# TDA7000_SCH.net
KiCad netlist of a schematic drawn in Altium Designer
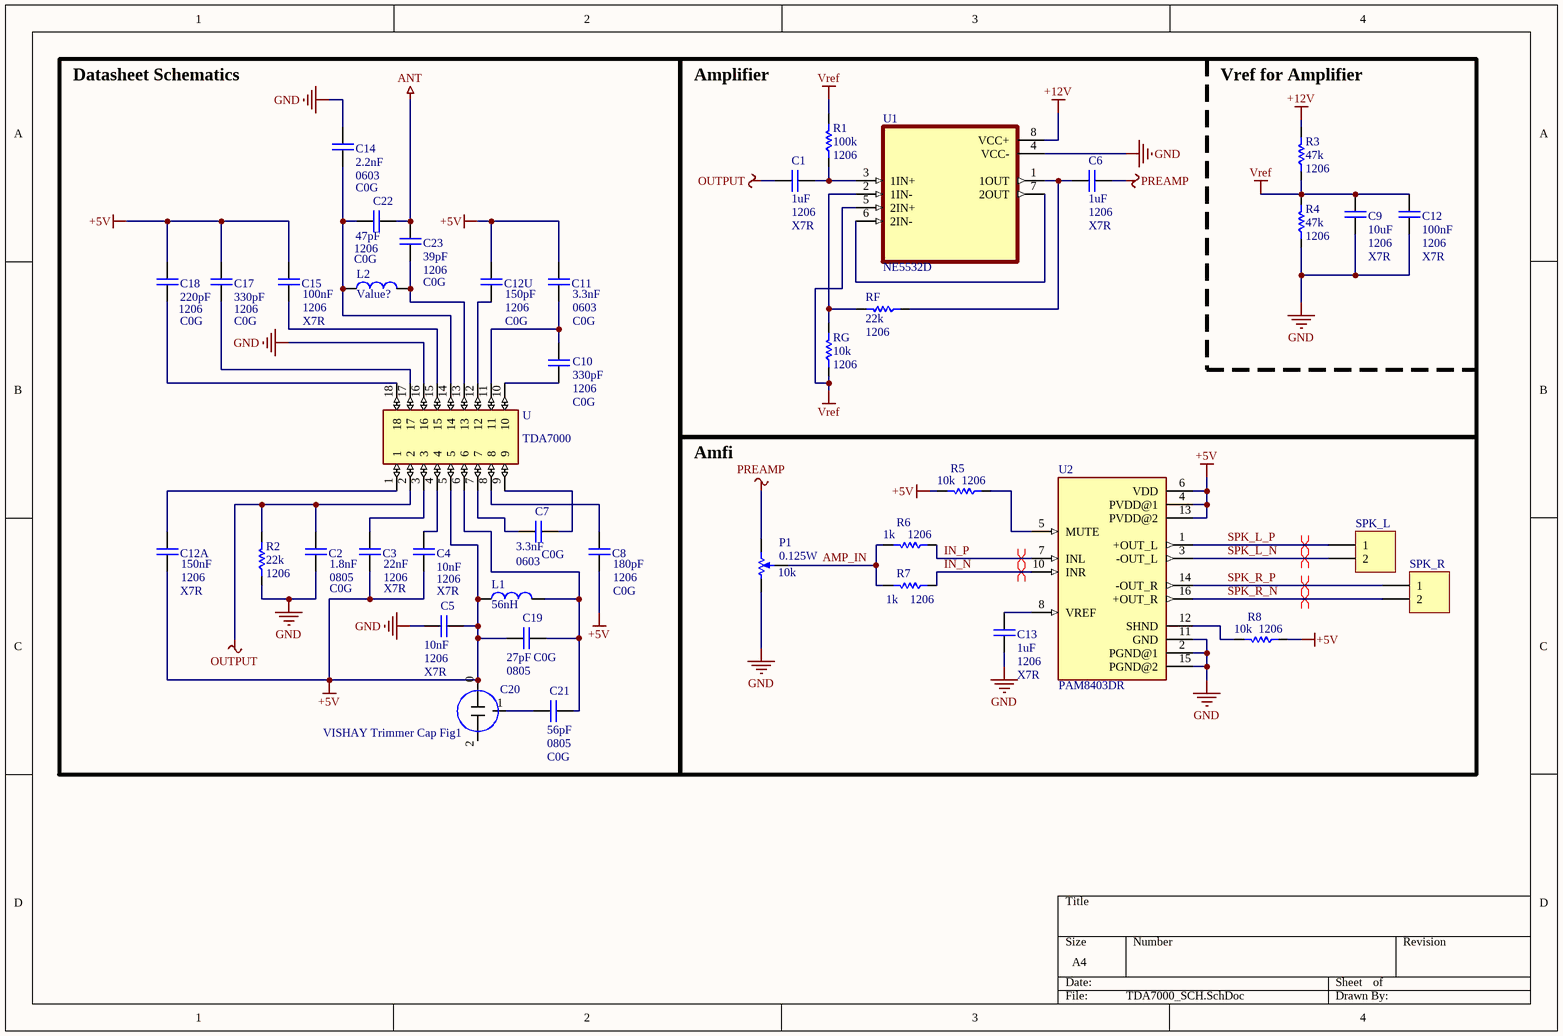
[diagram p0: TDA7000_SCH.SchDoc]

(export (version "E")
  (design (tool "Eeschema 10.0.6"))
  (components
    (comp (ref "C1")
      (value "1uF")
      (footprint "CAP 1206/3216")
      (description "Bipolar ceramic capacitor SMD")
      (fields
        (field (name "PACKAGE") "1206")
        (field (name "RATING") "X7R")
        (field (name "VALIDATION") "Valid")
      )
      (libsource (lib "aKaReZa") (part "Cap_Multi_SMD"))
    )
    (comp (ref "C2")
      (value "1.8nF")
      (footprint "CAP 0805/2012")
      (description "Bipolar ceramic capacitor SMD")
      (fields
        (field (name "PACKAGE") "0805")
        (field (name "RATING") "C0G")
        (field (name "VALIDATION") "Valid")
      )
      (libsource (lib "aKaReZa") (part "Cap_Multi_SMD"))
    )
    (comp (ref "C3")
      (value "22nF")
      (footprint "CAP 1206/3216")
      (description "Bipolar ceramic capacitor SMD")
      (fields
        (field (name "PACKAGE") "1206")
        (field (name "RATING") "X7R")
        (field (name "VALIDATION") "Valid")
      )
      (libsource (lib "aKaReZa") (part "Cap_Multi_SMD"))
    )
    (comp (ref "C4")
      (value "10nF")
      (footprint "CAP 1206/3216")
      (description "Bipolar ceramic capacitor SMD")
      (fields
        (field (name "PACKAGE") "1206")
        (field (name "RATING") "X7R")
        (field (name "VALIDATION") "Valid")
      )
      (libsource (lib "aKaReZa") (part "Cap_Multi_SMD"))
    )
    (comp (ref "C5")
      (value "10nF")
      (footprint "CAP 1206/3216")
      (description "Bipolar ceramic capacitor SMD")
      (fields
        (field (name "PACKAGE") "1206")
        (field (name "RATING") "X7R")
        (field (name "VALIDATION") "Valid")
      )
      (libsource (lib "aKaReZa") (part "Cap_Multi_SMD"))
    )
    (comp (ref "C6")
      (value "1uF")
      (footprint "CAP 1206/3216")
      (description "Bipolar ceramic capacitor SMD")
      (fields
        (field (name "PACKAGE") "1206")
        (field (name "RATING") "X7R")
        (field (name "VALIDATION") "Valid")
      )
      (libsource (lib "aKaReZa") (part "Cap_Multi_SMD"))
    )
    (comp (ref "C7")
      (value "3.3nF")
      (footprint "CAP 0603/1608")
      (description "Bipolar ceramic capacitor SMD")
      (fields
        (field (name "PACKAGE") "0603")
        (field (name "RATING") "C0G")
        (field (name "VALIDATION") "Valid")
      )
      (libsource (lib "aKaReZa") (part "Cap_Multi_SMD"))
    )
    (comp (ref "C8")
      (value "180pF")
      (footprint "CAP 1206/3216")
      (description "Bipolar ceramic capacitor SMD")
      (fields
        (field (name "PACKAGE") "1206")
        (field (name "RATING") "C0G")
        (field (name "VALIDATION") "Valid")
      )
      (libsource (lib "aKaReZa") (part "Cap_Multi_SMD"))
    )
    (comp (ref "C9")
      (value "10uF")
      (footprint "CAP 1206/3216")
      (description "Bipolar ceramic capacitor SMD")
      (fields
        (field (name "PACKAGE") "1206")
        (field (name "RATING") "X7R")
        (field (name "VALIDATION") "Valid")
      )
      (libsource (lib "aKaReZa") (part "Cap_Multi_SMD"))
    )
    (comp (ref "C10")
      (value "330pF")
      (footprint "CAP 1206/3216")
      (description "Bipolar ceramic capacitor SMD")
      (fields
        (field (name "PACKAGE") "1206")
        (field (name "RATING") "C0G")
        (field (name "VALIDATION") "Valid")
      )
      (libsource (lib "aKaReZa") (part "Cap_Multi_SMD"))
    )
    (comp (ref "C11")
      (value "3.3nF")
      (footprint "CAP 0603/1608")
      (description "Bipolar ceramic capacitor SMD")
      (fields
        (field (name "PACKAGE") "0603")
        (field (name "RATING") "C0G")
        (field (name "VALIDATION") "Valid")
      )
      (libsource (lib "aKaReZa") (part "Cap_Multi_SMD"))
    )
    (comp (ref "C12")
      (value "100nF")
      (footprint "CAP 1206/3216")
      (description "Bipolar ceramic capacitor SMD")
      (fields
        (field (name "PACKAGE") "1206")
        (field (name "RATING") "X7R")
        (field (name "VALIDATION") "Valid")
      )
      (libsource (lib "aKaReZa") (part "Cap_Multi_SMD"))
    )
    (comp (ref "C12A")
      (value "150nF")
      (footprint "CAP 1206/3216")
      (description "Bipolar ceramic capacitor SMD")
      (fields
        (field (name "PACKAGE") "1206")
        (field (name "RATING") "X7R")
        (field (name "VALIDATION") "Valid")
      )
      (libsource (lib "aKaReZa") (part "Cap_Multi_SMD"))
    )
    (comp (ref "C12U")
      (value "150pF")
      (footprint "CAP 1206/3216")
      (description "Bipolar ceramic capacitor SMD")
      (fields
        (field (name "PACKAGE") "1206")
        (field (name "RATING") "C0G")
        (field (name "VALIDATION") "Valid")
      )
      (libsource (lib "aKaReZa") (part "Cap_Multi_SMD"))
    )
    (comp (ref "C13")
      (value "1uF")
      (footprint "CAP 1206/3216")
      (description "Bipolar ceramic capacitor SMD")
      (fields
        (field (name "PACKAGE") "1206")
        (field (name "RATING") "X7R")
        (field (name "VALIDATION") "Valid")
      )
      (libsource (lib "aKaReZa") (part "Cap_Multi_SMD"))
    )
    (comp (ref "C14")
      (value "2.2nF")
      (footprint "CAP 0603/1608")
      (description "Bipolar ceramic capacitor SMD")
      (fields
        (field (name "PACKAGE") "0603")
        (field (name "RATING") "C0G")
        (field (name "VALIDATION") "Valid")
      )
      (libsource (lib "aKaReZa") (part "Cap_Multi_SMD"))
    )
    (comp (ref "C15")
      (value "100nF")
      (footprint "CAP 1206/3216")
      (description "Bipolar ceramic capacitor SMD")
      (fields
        (field (name "PACKAGE") "1206")
        (field (name "RATING") "X7R")
        (field (name "VALIDATION") "Valid")
      )
      (libsource (lib "aKaReZa") (part "Cap_Multi_SMD"))
    )
    (comp (ref "C17")
      (value "330pF")
      (footprint "CAP 1206/3216")
      (description "Bipolar ceramic capacitor SMD")
      (fields
        (field (name "PACKAGE") "1206")
        (field (name "RATING") "C0G")
        (field (name "VALIDATION") "Valid")
      )
      (libsource (lib "aKaReZa") (part "Cap_Multi_SMD"))
    )
    (comp (ref "C18")
      (value "220pF")
      (footprint "CAP 1206/3216")
      (description "Bipolar ceramic capacitor SMD")
      (fields
        (field (name "PACKAGE") "1206")
        (field (name "RATING") "C0G")
        (field (name "VALIDATION") "Valid")
      )
      (libsource (lib "aKaReZa") (part "Cap_Multi_SMD"))
    )
    (comp (ref "C19")
      (value "27pF")
      (footprint "CAP 1206/3216")
      (description "Bipolar ceramic capacitor SMD")
      (fields
        (field (name "PACKAGE") "0805")
        (field (name "RATING") "C0G")
        (field (name "VALIDATION") "Valid")
      )
      (libsource (lib "aKaReZa") (part "Cap_Multi_SMD"))
    )
    (comp (ref "C20")
      (value "VISHAY Trimmer Cap Fig1")
      (footprint "FIG2")
      (libsource (lib "10 mm Film Dielectric Trimmer") (part "VISHAY Trimmer Cap Fig1"))
    )
    (comp (ref "C21")
      (value "56pF")
      (footprint "CAP 0805/2012")
      (description "Bipolar ceramic capacitor SMD")
      (fields
        (field (name "PACKAGE") "0805")
        (field (name "RATING") "C0G")
        (field (name "VALIDATION") "Valid")
      )
      (libsource (lib "aKaReZa") (part "Cap_Multi_SMD"))
    )
    (comp (ref "C22")
      (value "47pF")
      (footprint "CAP 1206/3216")
      (description "Bipolar ceramic capacitor SMD")
      (fields
        (field (name "PACKAGE") "1206")
        (field (name "RATING") "C0G")
        (field (name "VALIDATION") "Valid")
      )
      (libsource (lib "aKaReZa") (part "Cap_Multi_SMD"))
    )
    (comp (ref "C23")
      (value "39pF")
      (footprint "CAP 1206/3216")
      (description "Bipolar ceramic capacitor SMD")
      (fields
        (field (name "PACKAGE") "1206")
        (field (name "RATING") "C0G")
        (field (name "VALIDATION") "Valid")
      )
      (libsource (lib "aKaReZa") (part "Cap_Multi_SMD"))
    )
    (comp (ref "L1")
      (value "56nH")
      (footprint "Inductor - 10uH (1/8)")
      (description "Inductor")
      (fields (field (name "VALIDATION") "NT"))
      (libsource (lib "aKaReZa") (part "Ind_THT"))
    )
    (comp (ref "L2")
      (value "Value?")
      (footprint "Inductor - 10uH (1/8)")
      (description "Inductor")
      (fields (field (name "VALIDATION") "NT"))
      (libsource (lib "aKaReZa") (part "Ind_THT"))
    )
    (comp (ref "P1")
      (value "10k")
      (footprint "POT_WH148")
      (description "Potentiometer")
      (fields (field (name "RATING") "0.125W") (field (name "VALIDATION") "Valid"))
      (libsource (lib "aKaReZa") (part "Res_Pot"))
    )
    (comp (ref "R1")
      (value "100k")
      (footprint "RES 1206 (3216X08L)")
      (description "Resistor")
      (fields (field (name "PACKAGE") "1206") (field (name "VALIDATION") "Valid"))
      (libsource (lib "aKaReZa") (part "Res_SMD"))
    )
    (comp (ref "R2")
      (value "22k")
      (footprint "RES 1206 (3216X08L)")
      (description "Resistor")
      (fields (field (name "PACKAGE") "1206") (field (name "VALIDATION") "Valid"))
      (libsource (lib "aKaReZa") (part "Res_SMD"))
    )
    (comp (ref "R3")
      (value "47k")
      (footprint "RES 1206 (3216X08L)")
      (description "Resistor")
      (fields (field (name "PACKAGE") "1206") (field (name "VALIDATION") "Valid"))
      (libsource (lib "aKaReZa") (part "Res_SMD"))
    )
    (comp (ref "R4")
      (value "47k")
      (footprint "RES 1206 (3216X08L)")
      (description "Resistor")
      (fields (field (name "PACKAGE") "1206") (field (name "VALIDATION") "Valid"))
      (libsource (lib "aKaReZa") (part "Res_SMD"))
    )
    (comp (ref "R5")
      (value "10k")
      (footprint "RES 1206 (3216X08L)")
      (description "Resistor")
      (fields (field (name "PACKAGE") "1206") (field (name "VALIDATION") "Valid"))
      (libsource (lib "aKaReZa") (part "Res_SMD"))
    )
    (comp (ref "R6")
      (value "1k")
      (footprint "RES 1206 (3216X08L)")
      (description "Resistor")
      (fields (field (name "PACKAGE") "1206") (field (name "VALIDATION") "Valid"))
      (libsource (lib "aKaReZa") (part "Res_SMD"))
    )
    (comp (ref "R7")
      (value "1k")
      (footprint "RES 1206 (3216X08L)")
      (description "Resistor")
      (fields (field (name "PACKAGE") "1206") (field (name "VALIDATION") "Valid"))
      (libsource (lib "aKaReZa") (part "Res_SMD"))
    )
    (comp (ref "R8")
      (value "10k")
      (footprint "RES 1206 (3216X08L)")
      (description "Resistor")
      (fields (field (name "PACKAGE") "1206") (field (name "VALIDATION") "Valid"))
      (libsource (lib "aKaReZa") (part "Res_SMD"))
    )
    (comp (ref "RF")
      (value "22k")
      (footprint "RES 1206 (3216X08L)")
      (description "Resistor")
      (fields (field (name "PACKAGE") "1206") (field (name "VALIDATION") "Valid"))
      (libsource (lib "aKaReZa") (part "Res_SMD"))
    )
    (comp (ref "RG")
      (value "10k")
      (footprint "RES 1206 (3216X08L)")
      (description "Resistor")
      (fields (field (name "PACKAGE") "1206") (field (name "VALIDATION") "Valid"))
      (libsource (lib "aKaReZa") (part "Res_SMD"))
    )
    (comp (ref "SPK_L")
      (value "2")
      (footprint "HDR_THT_2F_2.54mm")
      (description "Header, single row, 2 pin")
      (fields (field (name "VALIDATION") "NT"))
      (libsource (lib "aKaReZa") (part "Con_FPH_2x1_V_THT_2.54"))
    )
    (comp (ref "SPK_R")
      (value "2")
      (footprint "HDR_THT_2F_2.54mm")
      (description "Header, single row, 2 pin")
      (fields (field (name "VALIDATION") "NT"))
      (libsource (lib "aKaReZa") (part "Con_FPH_2x1_V_THT_2.54"))
    )
    (comp (ref "U")
      (value "TDA7000")
      (footprint "DIP802W45P254L2180H470Q18")
      (fields (field (name "MF") "MCM Electronics"))
      (libsource (lib "TDA7000") (part "TDA7000"))
    )
    (comp (ref "U1")
      (value "NE5532D")
      (footprint "SOIC127P599X175-8N")
      (description "Dual, 30-V, 10-MHz, low-noise operational amplifier for audio applications")
      (fields (field (name "MF") "Texas Instruments"))
      (libsource (lib "NE5532D") (part "NE5532D"))
    )
    (comp (ref "U2")
      (value "PAM8403DR")
      (footprint "SOIC127P605X150-16N")
      (description "Amplifiers, Audio, 3W STEREO FILTERLESS CLASS-D AUDIO AMP ¦ Diodes Inc PAM8403DR")
      (fields (field (name "MF") "Diodes Inc."))
      (libsource (lib "PAM8403DR") (part "PAM8403DR"))
    )
  )
  (nets
    (net (code "1") (name "+5V") (class "Default")
      (node (ref "C11") (pin "2") (pinfunction "2_2") (pintype "passive"))
      (node (ref "C12A") (pin "2") (pinfunction "2_2") (pintype "passive"))
      (node (ref "C12U") (pin "2") (pinfunction "2_2") (pintype "passive"))
      (node (ref "C15") (pin "1") (pinfunction "1_1") (pintype "passive"))
      (node (ref "C17") (pin "1") (pinfunction "1_1") (pintype "passive"))
      (node (ref "C18") (pin "1") (pinfunction "1_1") (pintype "passive"))
      (node (ref "C19") (pin "1") (pinfunction "1_1") (pintype "passive"))
      (node (ref "C20") (pin "0") (pinfunction "0_0") (pintype "passive"))
      (node (ref "C3") (pin "2") (pinfunction "2_2") (pintype "passive"))
      (node (ref "C4") (pin "2") (pinfunction "2_2") (pintype "passive"))
      (node (ref "C5") (pin "2") (pinfunction "2_2") (pintype "passive"))
      (node (ref "C8") (pin "1") (pinfunction "1_1") (pintype "passive"))
      (node (ref "L1") (pin "1") (pinfunction "1_1") (pintype "passive"))
      (node (ref "R5") (pin "2") (pinfunction "2_2") (pintype "passive"))
      (node (ref "R8") (pin "1") (pinfunction "1_1") (pintype "passive"))
      (node (ref "U") (pin "5") (pinfunction "5_5") (pintype "bidirectional"))
      (node (ref "U2") (pin "13") (pinfunction "PVDD@2_13") (pintype "power_in"))
      (node (ref "U2") (pin "4") (pinfunction "PVDD@1_4") (pintype "power_in"))
      (node (ref "U2") (pin "6") (pinfunction "VDD_6") (pintype "power_in"))
    )
    (net (code "2") (name "+12V") (class "Default")
      (node (ref "R3") (pin "2") (pinfunction "2_2") (pintype "passive"))
      (node (ref "U1") (pin "8") (pinfunction "VCC+_8") (pintype "power_in"))
    )
    (net (code "3") (name "/AMP_IN") (class "Default")
      (node (ref "P1") (pin "2") (pinfunction "WIPER_2") (pintype "passive"))
      (node (ref "R6") (pin "2") (pinfunction "2_2") (pintype "passive"))
      (node (ref "R7") (pin "2") (pinfunction "2_2") (pintype "passive"))
    )
    (net (code "4") (name "/IN_N") (class "Default")
      (node (ref "R7") (pin "1") (pinfunction "1_1") (pintype "passive"))
      (node (ref "U2") (pin "10") (pinfunction "INR_10") (pintype "input"))
    )
    (net (code "5") (name "/IN_P") (class "Default")
      (node (ref "R6") (pin "1") (pinfunction "1_1") (pintype "passive"))
      (node (ref "U2") (pin "7") (pinfunction "INL_7") (pintype "input"))
    )
    (net (code "6") (name "/SPK_L_N") (class "Default")
      (node (ref "SPK_L") (pin "2") (pinfunction "2_2") (pintype "passive"))
      (node (ref "U2") (pin "3") (pinfunction "-OUT_L_3") (pintype "output"))
    )
    (net (code "7") (name "/SPK_L_P") (class "Default")
      (node (ref "SPK_L") (pin "1") (pinfunction "1_1") (pintype "passive"))
      (node (ref "U2") (pin "1") (pinfunction "+OUT_L_1") (pintype "output"))
    )
    (net (code "8") (name "/SPK_R_N") (class "Default")
      (node (ref "SPK_R") (pin "2") (pinfunction "2_2") (pintype "passive"))
      (node (ref "U2") (pin "16") (pinfunction "+OUT_R_16") (pintype "output"))
    )
    (net (code "9") (name "/SPK_R_P") (class "Default")
      (node (ref "SPK_R") (pin "1") (pinfunction "1_1") (pintype "passive"))
      (node (ref "U2") (pin "14") (pinfunction "-OUT_R_14") (pintype "output"))
    )
    (net (code "10") (name "ANT") (class "Default")
      (node (ref "C22") (pin "2") (pinfunction "2_2") (pintype "passive"))
      (node (ref "C23") (pin "2") (pinfunction "2_2") (pintype "passive"))
    )
    (net (code "11") (name "GND") (class "Default")
      (node (ref "C12") (pin "1") (pinfunction "1_1") (pintype "passive"))
      (node (ref "C13") (pin "1") (pinfunction "1_1") (pintype "passive"))
      (node (ref "C14") (pin "2") (pinfunction "2_2") (pintype "passive"))
      (node (ref "C2") (pin "2") (pinfunction "2_2") (pintype "passive"))
      (node (ref "C5") (pin "1") (pinfunction "1_1") (pintype "passive"))
      (node (ref "C9") (pin "1") (pinfunction "1_1") (pintype "passive"))
      (node (ref "P1") (pin "3") (pinfunction "CW_3") (pintype "passive"))
      (node (ref "R2") (pin "1") (pinfunction "1_1") (pintype "passive"))
      (node (ref "R4") (pin "1") (pinfunction "1_1") (pintype "passive"))
      (node (ref "U") (pin "16") (pinfunction "16_16") (pintype "bidirectional"))
      (node (ref "U1") (pin "4") (pinfunction "VCC-_4") (pintype "power_in"))
      (node (ref "U2") (pin "11") (pinfunction "GND_11") (pintype "power_in"))
      (node (ref "U2") (pin "15") (pinfunction "PGND@2_15") (pintype "power_in"))
      (node (ref "U2") (pin "2") (pinfunction "PGND@1_2") (pintype "power_in"))
    )
    (net (code "12") (name "Net-(C3-Pad1)") (class "Default")
      (node (ref "C3") (pin "1") (pinfunction "1_1") (pintype "passive"))
      (node (ref "U") (pin "3") (pinfunction "3_3") (pintype "bidirectional"))
    )
    (net (code "13") (name "Net-(C4-Pad1)") (class "Default")
      (node (ref "C4") (pin "1") (pinfunction "1_1") (pintype "passive"))
      (node (ref "U") (pin "4") (pinfunction "4_4") (pintype "bidirectional"))
    )
    (net (code "14") (name "Net-(C7-Pad1)") (class "Default")
      (node (ref "C7") (pin "1") (pinfunction "1_1") (pintype "passive"))
      (node (ref "U") (pin "7") (pinfunction "7_7") (pintype "bidirectional"))
    )
    (net (code "15") (name "Net-(C7-Pad2)") (class "Default")
      (node (ref "C7") (pin "2") (pinfunction "2_2") (pintype "passive"))
      (node (ref "U") (pin "9") (pinfunction "9_9") (pintype "bidirectional"))
    )
    (net (code "16") (name "Net-(C8-Pad2)") (class "Default")
      (node (ref "C8") (pin "2") (pinfunction "2_2") (pintype "passive"))
      (node (ref "U") (pin "8") (pinfunction "8_8") (pintype "bidirectional"))
    )
    (net (code "17") (name "Net-(C10-Pad1)") (class "Default")
      (node (ref "C10") (pin "1") (pinfunction "1_1") (pintype "passive"))
      (node (ref "U") (pin "10") (pinfunction "10_10") (pintype "bidirectional"))
    )
    (net (code "18") (name "Net-(C10-Pad2)") (class "Default")
      (node (ref "C10") (pin "2") (pinfunction "2_2") (pintype "passive"))
      (node (ref "C11") (pin "1") (pinfunction "1_1") (pintype "passive"))
      (node (ref "U") (pin "11") (pinfunction "11_11") (pintype "bidirectional"))
    )
    (net (code "19") (name "Net-(C12A-Pad1)") (class "Default")
      (node (ref "C12A") (pin "1") (pinfunction "1_1") (pintype "passive"))
      (node (ref "U") (pin "1") (pinfunction "1_1") (pintype "bidirectional"))
    )
    (net (code "20") (name "Net-(C12U-Pad1)") (class "Default")
      (node (ref "C12U") (pin "1") (pinfunction "1_1") (pintype "passive"))
      (node (ref "U") (pin "12") (pinfunction "12_12") (pintype "bidirectional"))
    )
    (net (code "21") (name "Net-(C14-Pad1)") (class "Default")
      (node (ref "C14") (pin "1") (pinfunction "1_1") (pintype "passive"))
      (node (ref "C22") (pin "1") (pinfunction "1_1") (pintype "passive"))
      (node (ref "L2") (pin "1") (pinfunction "1_1") (pintype "passive"))
      (node (ref "U") (pin "14") (pinfunction "14_14") (pintype "bidirectional"))
    )
    (net (code "22") (name "Net-(C15-Pad2)") (class "Default")
      (node (ref "C15") (pin "2") (pinfunction "2_2") (pintype "passive"))
      (node (ref "U") (pin "15") (pinfunction "15_15") (pintype "bidirectional"))
    )
    (net (code "23") (name "Net-(C17-Pad2)") (class "Default")
      (node (ref "C17") (pin "2") (pinfunction "2_2") (pintype "passive"))
      (node (ref "U") (pin "17") (pinfunction "17_17") (pintype "bidirectional"))
    )
    (net (code "24") (name "Net-(C18-Pad2)") (class "Default")
      (node (ref "C18") (pin "2") (pinfunction "2_2") (pintype "passive"))
      (node (ref "U") (pin "18") (pinfunction "18_18") (pintype "bidirectional"))
    )
    (net (code "25") (name "Net-(C19-Pad2)") (class "Default")
      (node (ref "C19") (pin "2") (pinfunction "2_2") (pintype "passive"))
      (node (ref "C21") (pin "2") (pinfunction "2_2") (pintype "passive"))
      (node (ref "L1") (pin "2") (pinfunction "2_2") (pintype "passive"))
      (node (ref "U") (pin "6") (pinfunction "6_6") (pintype "bidirectional"))
    )
    (net (code "26") (name "Net-(C20-Pad1)") (class "Default")
      (node (ref "C20") (pin "1") (pinfunction "1_1") (pintype "passive"))
      (node (ref "C21") (pin "1") (pinfunction "1_1") (pintype "passive"))
    )
    (net (code "27") (name "Net-(C23-Pad1)") (class "Default")
      (node (ref "C23") (pin "1") (pinfunction "1_1") (pintype "passive"))
      (node (ref "L2") (pin "2") (pinfunction "2_2") (pintype "passive"))
      (node (ref "U") (pin "13") (pinfunction "13_13") (pintype "bidirectional"))
    )
    (net (code "28") (name "Net-(U1-1IN+)") (class "Default")
      (node (ref "C1") (pin "2") (pinfunction "2_2") (pintype "passive"))
      (node (ref "R1") (pin "1") (pinfunction "1_1") (pintype "passive"))
      (node (ref "U1") (pin "3") (pinfunction "1IN+_3") (pintype "input"))
    )
    (net (code "29") (name "Net-(U1-1IN-)") (class "Default")
      (node (ref "RF") (pin "2") (pinfunction "2_2") (pintype "passive"))
      (node (ref "RG") (pin "2") (pinfunction "2_2") (pintype "passive"))
      (node (ref "U1") (pin "2") (pinfunction "1IN-_2") (pintype "input"))
    )
    (net (code "30") (name "Net-(U1-1OUT)") (class "Default")
      (node (ref "C6") (pin "1") (pinfunction "1_1") (pintype "passive"))
      (node (ref "RF") (pin "1") (pinfunction "1_1") (pintype "passive"))
      (node (ref "U1") (pin "1") (pinfunction "1OUT_1") (pintype "output"))
    )
    (net (code "31") (name "Net-(U1-2IN-)") (class "Default")
      (node (ref "U1") (pin "6") (pinfunction "2IN-_6") (pintype "input"))
      (node (ref "U1") (pin "7") (pinfunction "2OUT_7") (pintype "output"))
    )
    (net (code "32") (name "Net-(U2-MUTE)") (class "Default")
      (node (ref "R5") (pin "1") (pinfunction "1_1") (pintype "passive"))
      (node (ref "U2") (pin "5") (pinfunction "MUTE_5") (pintype "input"))
    )
    (net (code "33") (name "Net-(U2-SHND)") (class "Default")
      (node (ref "R8") (pin "2") (pinfunction "2_2") (pintype "passive"))
      (node (ref "U2") (pin "12") (pinfunction "SHND_12") (pintype "power_in"))
    )
    (net (code "34") (name "Net-(U2-VREF)") (class "Default")
      (node (ref "C13") (pin "2") (pinfunction "2_2") (pintype "passive"))
      (node (ref "U2") (pin "8") (pinfunction "VREF_8") (pintype "input"))
    )
    (net (code "35") (name "OUTPUT") (class "Default")
      (node (ref "C1") (pin "1") (pinfunction "1_1") (pintype "passive"))
      (node (ref "C2") (pin "1") (pinfunction "1_1") (pintype "passive"))
      (node (ref "R2") (pin "2") (pinfunction "2_2") (pintype "passive"))
      (node (ref "U") (pin "2") (pinfunction "2_2") (pintype "bidirectional"))
    )
    (net (code "36") (name "PREAMP") (class "Default")
      (node (ref "C6") (pin "2") (pinfunction "2_2") (pintype "passive"))
      (node (ref "P1") (pin "1") (pinfunction "CCW_1") (pintype "passive"))
    )
    (net (code "37") (name "Vref") (class "Default")
      (node (ref "C12") (pin "2") (pinfunction "2_2") (pintype "passive"))
      (node (ref "C9") (pin "2") (pinfunction "2_2") (pintype "passive"))
      (node (ref "R1") (pin "2") (pinfunction "2_2") (pintype "passive"))
      (node (ref "R3") (pin "1") (pinfunction "1_1") (pintype "passive"))
      (node (ref "R4") (pin "2") (pinfunction "2_2") (pintype "passive"))
      (node (ref "RG") (pin "1") (pinfunction "1_1") (pintype "passive"))
      (node (ref "U1") (pin "5") (pinfunction "2IN+_5") (pintype "input"))
    )
    (net (code "38") (name "unconnected-(C20-Pad2)") (class "Default")
      (node (ref "C20") (pin "2") (pinfunction "2_2") (pintype "passive"))
    )
  )
)
